# Sheet2.net
KiCad netlist of a schematic drawn in Altium Designer
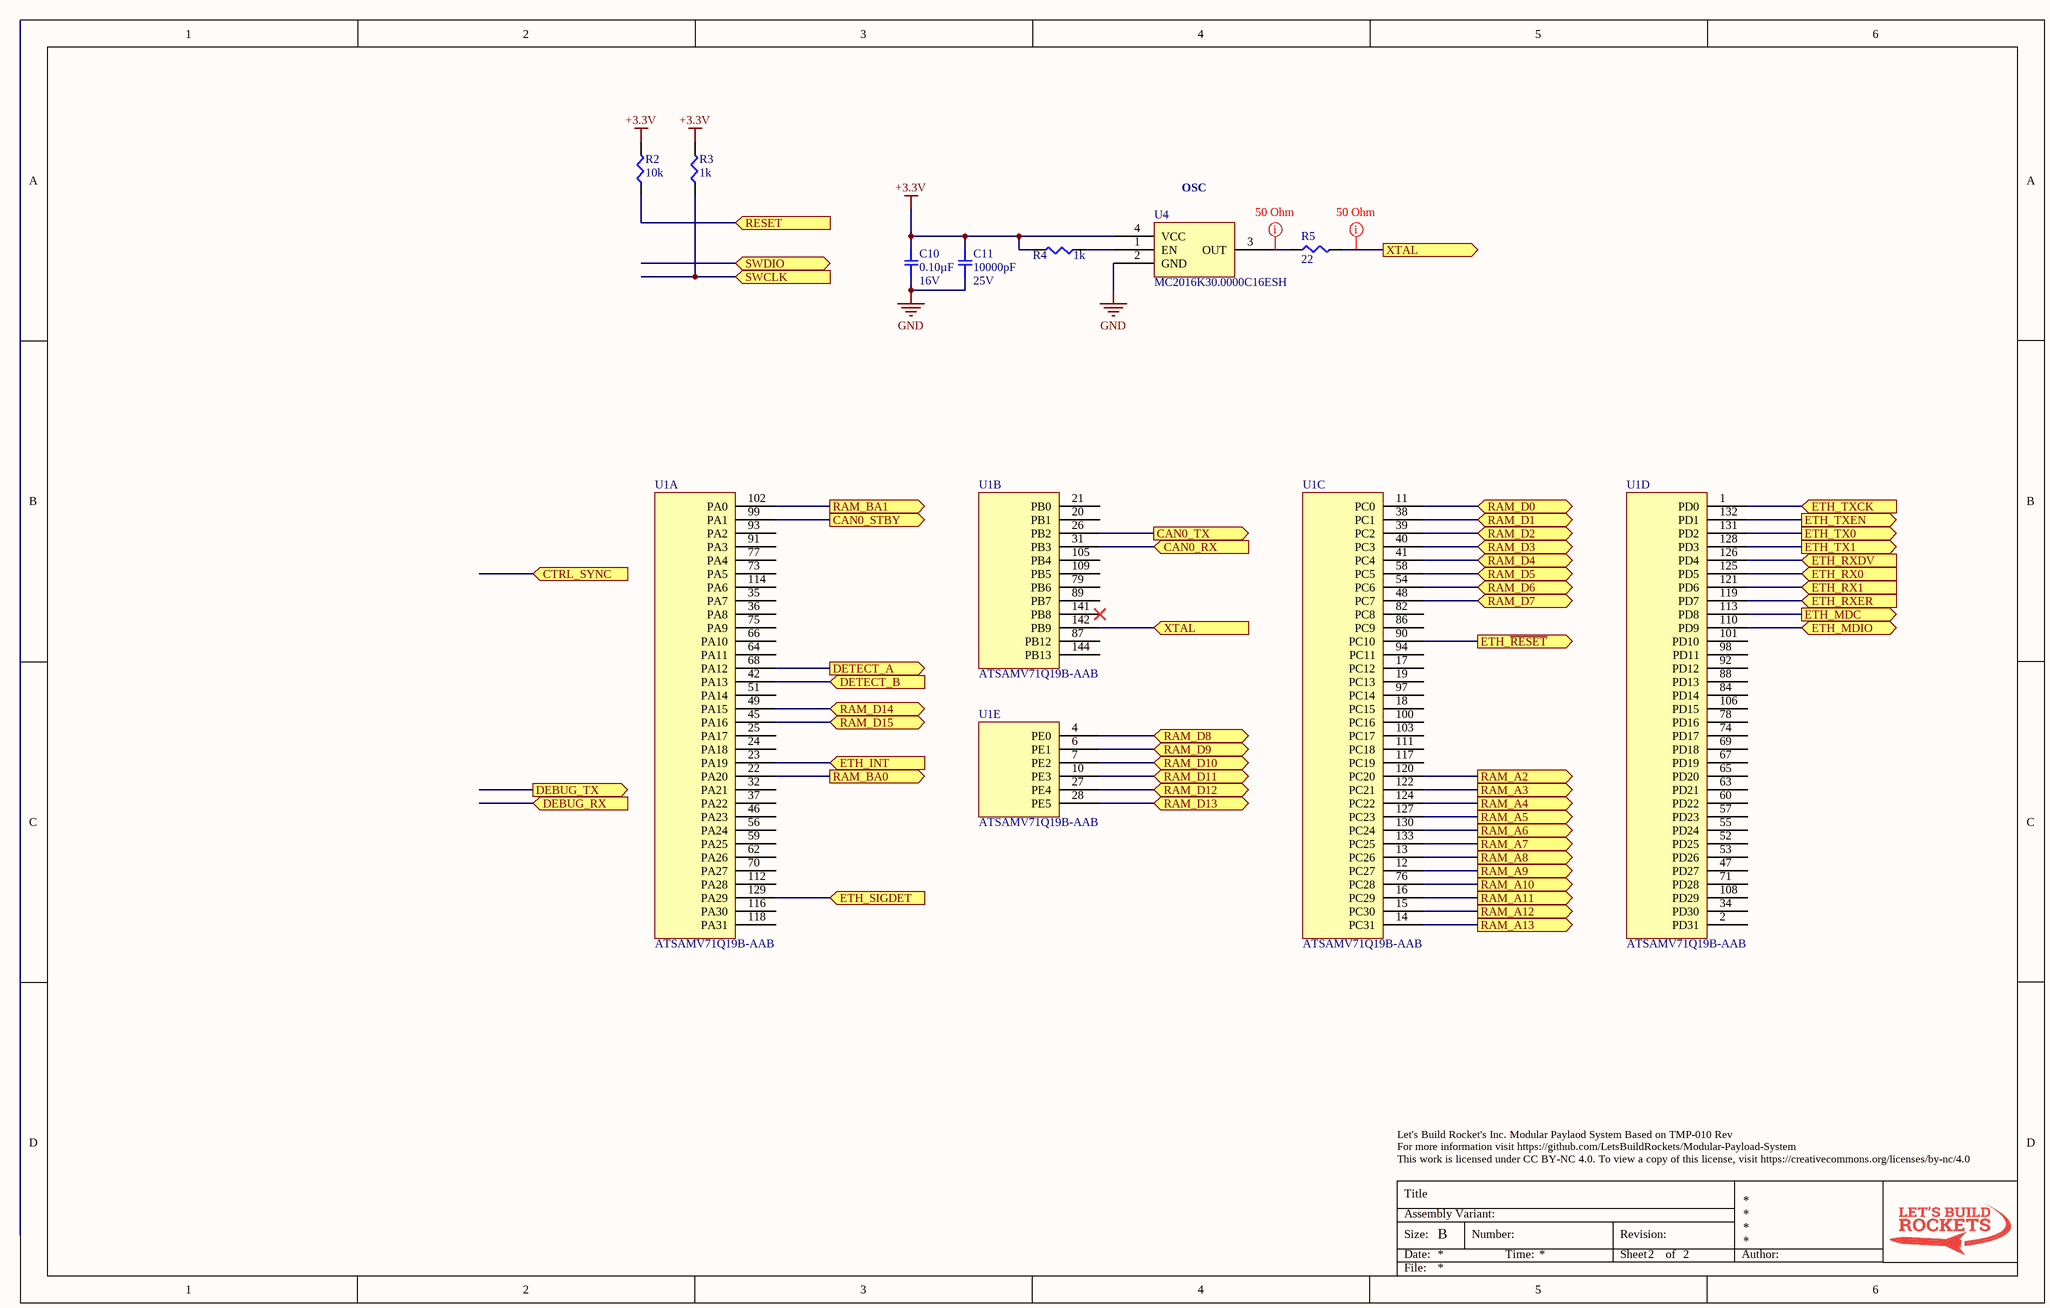
[diagram p0: Sheet2.SchDoc]

(export (version "E")
  (design (tool "Eeschema 10.0.6"))
  (components
    (comp (ref "C10")
      (value "0.10µF")
      (footprint "SMD-0402C")
      (description "CAP CER 0.1UF 16V X7R 0402")
      (fields
        (field (name "DIGI-KEY PART NUMBER") "490-4759-1-ND")
        (field (name "PART NUMBER") "GCM155R71C104KA55D")
        (field (name "VOLTAGE") "16V")
      )
      (libsource (lib "capacitor_murata_0402") (part "GCM155R71C104KA55D"))
    )
    (comp (ref "C11")
      (value "10000pF")
      (footprint "SMD-0402C")
      (description "CAP CER 10000PF 25V X7R 0402")
      (fields
        (field (name "DIGI-KEY PART NUMBER") "490-6043-1-ND")
        (field (name "PART NUMBER") "GCM155R71E103KA37D")
        (field (name "VOLTAGE") "25V")
      )
      (libsource (lib "capacitor_murata_0402") (part "GCM155R71E103KA37D"))
    )
    (comp (ref "R2")
      (value "10k")
      (footprint "SMD-0402-RES")
      (description "RES SMD 10K OHM 5% 1/10W 0402")
      (fields (field (name "PART NUMBER") "ERJ-2GEJ103X") (field (name "DIGI-KEY PART NUMBER") "P10KJCT-ND"))
      (libsource (lib "Panasonic_ERJ_0402") (part "ERJ-2GEJ103X"))
    )
    (comp (ref "R3")
      (value "1k")
      (footprint "SMD-0402-RES")
      (description "RES SMD 1K OHM 5% 1/10W 0402")
      (fields (field (name "PART NUMBER") "ERJ-2GEJ102X") (field (name "DIGI-KEY PART NUMBER") "P1.0KJCT-ND"))
      (libsource (lib "Panasonic_ERJ_0402") (part "ERJ-2GEJ102X"))
    )
    (comp (ref "R4")
      (value "1k")
      (footprint "SMD-0402-RES")
      (description "RES SMD 1K OHM 5% 1/10W 0402")
      (fields (field (name "PART NUMBER") "ERJ-2GEJ102X") (field (name "DIGI-KEY PART NUMBER") "P1.0KJCT-ND"))
      (libsource (lib "Panasonic_ERJ_0402") (part "ERJ-2GEJ102X"))
    )
    (comp (ref "R5")
      (value "22")
      (footprint "SMD-0402-RES")
      (description "RES SMD 22 OHM 1% 1/10W 0402")
      (fields
        (field (name "PART NUMBER") "ERJ-2RKF22R0X")
        (field (name "DIGI-KEY PART NUMBER") "P22.0LCT-ND")
      )
      (libsource (lib "Panasonic_ERJ_0402") (part "ERJ-2RKF22R0X"))
    )
    (comp (ref "U1")
      (value "ATSAMV71Q19B-AAB")
      (footprint "TSQFP50P2200X2200X160-144N")
      (libsource (lib "ModularPayload") (part "ATSAMV71Q19B-AAB"))
    )
    (comp (ref "U4")
      (value "MC2016K30.0000C16ESH")
      (footprint "MC2016")
      (libsource (lib "ModularPayload") (part "MC2016K30.0000C16ESH"))
    )
  )
  (nets
    (net (code "1") (name "+3.3V") (class "Default")
      (node (ref "C10") (pin "2") (pinfunction "2_2") (pintype "passive"))
      (node (ref "C11") (pin "2") (pinfunction "2_2") (pintype "passive"))
      (node (ref "R2") (pin "2") (pinfunction "2_2") (pintype "passive"))
      (node (ref "R3") (pin "2") (pinfunction "2_2") (pintype "passive"))
      (node (ref "R4") (pin "2") (pinfunction "2_2") (pintype "passive"))
      (node (ref "U4") (pin "4") (pinfunction "VCC_4") (pintype "passive"))
    )
    (net (code "2") (name "/CAN0_RX") (class "Default")
      (node (ref "U1") (pin "31") (pinfunction "PB3_31") (pintype "passive"))
    )
    (net (code "3") (name "/CAN0_STBY") (class "Default")
      (node (ref "U1") (pin "99") (pinfunction "PA1_99") (pintype "passive"))
    )
    (net (code "4") (name "/CAN0_TX") (class "Default")
      (node (ref "U1") (pin "26") (pinfunction "PB2_26") (pintype "passive"))
    )
    (net (code "8") (name "/DETECT_A") (class "Default")
      (node (ref "U1") (pin "68") (pinfunction "PA12_68") (pintype "passive"))
    )
    (net (code "9") (name "/DETECT_B") (class "Default")
      (node (ref "U1") (pin "42") (pinfunction "PA13_42") (pintype "passive"))
    )
    (net (code "10") (name "/ETH_INT") (class "Default")
      (node (ref "U1") (pin "23") (pinfunction "PA19_23") (pintype "passive"))
    )
    (net (code "11") (name "/ETH_MDC") (class "Default")
      (node (ref "U1") (pin "113") (pinfunction "PD8_113") (pintype "passive"))
    )
    (net (code "12") (name "/ETH_MDIO") (class "Default")
      (node (ref "U1") (pin "110") (pinfunction "PD9_110") (pintype "passive"))
    )
    (net (code "13") (name "/ETH_RX0") (class "Default")
      (node (ref "U1") (pin "125") (pinfunction "PD5_125") (pintype "passive"))
    )
    (net (code "14") (name "/ETH_RX1") (class "Default")
      (node (ref "U1") (pin "121") (pinfunction "PD6_121") (pintype "passive"))
    )
    (net (code "15") (name "/ETH_RXDV") (class "Default")
      (node (ref "U1") (pin "126") (pinfunction "PD4_126") (pintype "passive"))
    )
    (net (code "16") (name "/ETH_RXER") (class "Default")
      (node (ref "U1") (pin "119") (pinfunction "PD7_119") (pintype "passive"))
    )
    (net (code "17") (name "/ETH_SIGDET") (class "Default")
      (node (ref "U1") (pin "129") (pinfunction "PA29_129") (pintype "passive"))
    )
    (net (code "18") (name "/ETH_TX0") (class "Default")
      (node (ref "U1") (pin "131") (pinfunction "PD2_131") (pintype "passive"))
    )
    (net (code "19") (name "/ETH_TX1") (class "Default")
      (node (ref "U1") (pin "128") (pinfunction "PD3_128") (pintype "passive"))
    )
    (net (code "20") (name "/ETH_TXCK") (class "Default")
      (node (ref "U1") (pin "1") (pinfunction "PD0_1") (pintype "passive"))
    )
    (net (code "21") (name "/ETH_TXEN") (class "Default")
      (node (ref "U1") (pin "132") (pinfunction "PD1_132") (pintype "passive"))
    )
    (net (code "22") (name "/ETH_~{RESET}") (class "Default")
      (node (ref "U1") (pin "90") (pinfunction "PC10_90") (pintype "passive"))
    )
    (net (code "23") (name "/RAM_A2") (class "Default")
      (node (ref "U1") (pin "120") (pinfunction "PC20_120") (pintype "passive"))
    )
    (net (code "24") (name "/RAM_A3") (class "Default")
      (node (ref "U1") (pin "122") (pinfunction "PC21_122") (pintype "passive"))
    )
    (net (code "25") (name "/RAM_A4") (class "Default")
      (node (ref "U1") (pin "124") (pinfunction "PC22_124") (pintype "passive"))
    )
    (net (code "26") (name "/RAM_A5") (class "Default")
      (node (ref "U1") (pin "127") (pinfunction "PC23_127") (pintype "passive"))
    )
    (net (code "27") (name "/RAM_A6") (class "Default")
      (node (ref "U1") (pin "130") (pinfunction "PC24_130") (pintype "passive"))
    )
    (net (code "28") (name "/RAM_A7") (class "Default")
      (node (ref "U1") (pin "133") (pinfunction "PC25_133") (pintype "passive"))
    )
    (net (code "29") (name "/RAM_A8") (class "Default")
      (node (ref "U1") (pin "13") (pinfunction "PC26_13") (pintype "passive"))
    )
    (net (code "30") (name "/RAM_A9") (class "Default")
      (node (ref "U1") (pin "12") (pinfunction "PC27_12") (pintype "passive"))
    )
    (net (code "31") (name "/RAM_A10") (class "Default")
      (node (ref "U1") (pin "76") (pinfunction "PC28_76") (pintype "passive"))
    )
    (net (code "32") (name "/RAM_A11") (class "Default")
      (node (ref "U1") (pin "16") (pinfunction "PC29_16") (pintype "passive"))
    )
    (net (code "33") (name "/RAM_A12") (class "Default")
      (node (ref "U1") (pin "15") (pinfunction "PC30_15") (pintype "passive"))
    )
    (net (code "34") (name "/RAM_A13") (class "Default")
      (node (ref "U1") (pin "14") (pinfunction "PC31_14") (pintype "passive"))
    )
    (net (code "35") (name "/RAM_BA0") (class "Default")
      (node (ref "U1") (pin "22") (pinfunction "PA20_22") (pintype "passive"))
    )
    (net (code "36") (name "/RAM_BA1") (class "Default")
      (node (ref "U1") (pin "102") (pinfunction "PA0_102") (pintype "passive"))
    )
    (net (code "37") (name "/RAM_D0") (class "Default")
      (node (ref "U1") (pin "11") (pinfunction "PC0_11") (pintype "passive"))
    )
    (net (code "38") (name "/RAM_D1") (class "Default")
      (node (ref "U1") (pin "38") (pinfunction "PC1_38") (pintype "passive"))
    )
    (net (code "39") (name "/RAM_D2") (class "Default")
      (node (ref "U1") (pin "39") (pinfunction "PC2_39") (pintype "passive"))
    )
    (net (code "40") (name "/RAM_D3") (class "Default")
      (node (ref "U1") (pin "40") (pinfunction "PC3_40") (pintype "passive"))
    )
    (net (code "41") (name "/RAM_D4") (class "Default")
      (node (ref "U1") (pin "41") (pinfunction "PC4_41") (pintype "passive"))
    )
    (net (code "42") (name "/RAM_D5") (class "Default")
      (node (ref "U1") (pin "58") (pinfunction "PC5_58") (pintype "passive"))
    )
    (net (code "43") (name "/RAM_D6") (class "Default")
      (node (ref "U1") (pin "54") (pinfunction "PC6_54") (pintype "passive"))
    )
    (net (code "44") (name "/RAM_D7") (class "Default")
      (node (ref "U1") (pin "48") (pinfunction "PC7_48") (pintype "passive"))
    )
    (net (code "45") (name "/RAM_D8") (class "Default")
      (node (ref "U1") (pin "4") (pinfunction "PE0_4") (pintype "passive"))
    )
    (net (code "46") (name "/RAM_D9") (class "Default")
      (node (ref "U1") (pin "6") (pinfunction "PE1_6") (pintype "passive"))
    )
    (net (code "47") (name "/RAM_D10") (class "Default")
      (node (ref "U1") (pin "7") (pinfunction "PE2_7") (pintype "passive"))
    )
    (net (code "48") (name "/RAM_D11") (class "Default")
      (node (ref "U1") (pin "10") (pinfunction "PE3_10") (pintype "passive"))
    )
    (net (code "49") (name "/RAM_D12") (class "Default")
      (node (ref "U1") (pin "27") (pinfunction "PE4_27") (pintype "passive"))
    )
    (net (code "50") (name "/RAM_D13") (class "Default")
      (node (ref "U1") (pin "28") (pinfunction "PE5_28") (pintype "passive"))
    )
    (net (code "51") (name "/RAM_D14") (class "Default")
      (node (ref "U1") (pin "49") (pinfunction "PA15_49") (pintype "passive"))
    )
    (net (code "52") (name "/RAM_D15") (class "Default")
      (node (ref "U1") (pin "45") (pinfunction "PA16_45") (pintype "passive"))
    )
    (net (code "53") (name "/RESET") (class "Default")
      (node (ref "R2") (pin "1") (pinfunction "1_1") (pintype "passive"))
    )
    (net (code "54") (name "/SWCLK") (class "Default")
      (node (ref "R3") (pin "1") (pinfunction "1_1") (pintype "passive"))
    )
    (net (code "56") (name "/XTAL") (class "Default")
      (node (ref "R5") (pin "2") (pinfunction "2_2") (pintype "passive"))
      (node (ref "U1") (pin "142") (pinfunction "PB9_142") (pintype "passive"))
    )
    (net (code "57") (name "GND") (class "Default")
      (node (ref "C10") (pin "1") (pinfunction "1_1") (pintype "passive"))
      (node (ref "C11") (pin "1") (pinfunction "1_1") (pintype "passive"))
      (node (ref "U4") (pin "2") (pinfunction "GND_2") (pintype "passive"))
    )
    (net (code "58") (name "Net-(U4-EN)") (class "Default")
      (node (ref "R4") (pin "1") (pinfunction "1_1") (pintype "passive"))
      (node (ref "U4") (pin "1") (pinfunction "EN_1") (pintype "passive"))
    )
    (net (code "59") (name "Net-(U4-OUT)") (class "Default")
      (node (ref "R5") (pin "1") (pinfunction "1_1") (pintype "passive"))
      (node (ref "U4") (pin "3") (pinfunction "OUT_3") (pintype "passive"))
    )
    (net (code "60") (name "unconnected-(U1A-PA2-Pad93)") (class "Default")
      (node (ref "U1") (pin "93") (pinfunction "PA2_93") (pintype "passive"))
    )
    (net (code "61") (name "unconnected-(U1A-PA3-Pad91)") (class "Default")
      (node (ref "U1") (pin "91") (pinfunction "PA3_91") (pintype "passive"))
    )
    (net (code "62") (name "unconnected-(U1A-PA4-Pad77)") (class "Default")
      (node (ref "U1") (pin "77") (pinfunction "PA4_77") (pintype "passive"))
    )
    (net (code "63") (name "unconnected-(U1A-PA5-Pad73)") (class "Default")
      (node (ref "U1") (pin "73") (pinfunction "PA5_73") (pintype "passive"))
    )
    (net (code "64") (name "unconnected-(U1A-PA6-Pad114)") (class "Default")
      (node (ref "U1") (pin "114") (pinfunction "PA6_114") (pintype "passive"))
    )
    (net (code "65") (name "unconnected-(U1A-PA7-Pad35)") (class "Default")
      (node (ref "U1") (pin "35") (pinfunction "PA7_35") (pintype "passive"))
    )
    (net (code "66") (name "unconnected-(U1A-PA8-Pad36)") (class "Default")
      (node (ref "U1") (pin "36") (pinfunction "PA8_36") (pintype "passive"))
    )
    (net (code "67") (name "unconnected-(U1A-PA9-Pad75)") (class "Default")
      (node (ref "U1") (pin "75") (pinfunction "PA9_75") (pintype "passive"))
    )
    (net (code "68") (name "unconnected-(U1A-PA10-Pad66)") (class "Default")
      (node (ref "U1") (pin "66") (pinfunction "PA10_66") (pintype "passive"))
    )
    (net (code "69") (name "unconnected-(U1A-PA11-Pad64)") (class "Default")
      (node (ref "U1") (pin "64") (pinfunction "PA11_64") (pintype "passive"))
    )
    (net (code "70") (name "unconnected-(U1A-PA14-Pad51)") (class "Default")
      (node (ref "U1") (pin "51") (pinfunction "PA14_51") (pintype "passive"))
    )
    (net (code "71") (name "unconnected-(U1A-PA17-Pad25)") (class "Default")
      (node (ref "U1") (pin "25") (pinfunction "PA17_25") (pintype "passive"))
    )
    (net (code "72") (name "unconnected-(U1A-PA18-Pad24)") (class "Default")
      (node (ref "U1") (pin "24") (pinfunction "PA18_24") (pintype "passive"))
    )
    (net (code "73") (name "unconnected-(U1A-PA21-Pad32)") (class "Default")
      (node (ref "U1") (pin "32") (pinfunction "PA21_32") (pintype "passive"))
    )
    (net (code "74") (name "unconnected-(U1A-PA22-Pad37)") (class "Default")
      (node (ref "U1") (pin "37") (pinfunction "PA22_37") (pintype "passive"))
    )
    (net (code "75") (name "unconnected-(U1A-PA23-Pad46)") (class "Default")
      (node (ref "U1") (pin "46") (pinfunction "PA23_46") (pintype "passive"))
    )
    (net (code "76") (name "unconnected-(U1A-PA24-Pad56)") (class "Default")
      (node (ref "U1") (pin "56") (pinfunction "PA24_56") (pintype "passive"))
    )
    (net (code "77") (name "unconnected-(U1A-PA25-Pad59)") (class "Default")
      (node (ref "U1") (pin "59") (pinfunction "PA25_59") (pintype "passive"))
    )
    (net (code "78") (name "unconnected-(U1A-PA26-Pad62)") (class "Default")
      (node (ref "U1") (pin "62") (pinfunction "PA26_62") (pintype "passive"))
    )
    (net (code "79") (name "unconnected-(U1A-PA27-Pad70)") (class "Default")
      (node (ref "U1") (pin "70") (pinfunction "PA27_70") (pintype "passive"))
    )
    (net (code "80") (name "unconnected-(U1A-PA28-Pad112)") (class "Default")
      (node (ref "U1") (pin "112") (pinfunction "PA28_112") (pintype "passive"))
    )
    (net (code "81") (name "unconnected-(U1A-PA30-Pad116)") (class "Default")
      (node (ref "U1") (pin "116") (pinfunction "PA30_116") (pintype "passive"))
    )
    (net (code "82") (name "unconnected-(U1A-PA31-Pad118)") (class "Default")
      (node (ref "U1") (pin "118") (pinfunction "PA31_118") (pintype "passive"))
    )
    (net (code "83") (name "unconnected-(U1B-PB0-Pad21)") (class "Default")
      (node (ref "U1") (pin "21") (pinfunction "PB0_21") (pintype "passive"))
    )
    (net (code "84") (name "unconnected-(U1B-PB1-Pad20)") (class "Default")
      (node (ref "U1") (pin "20") (pinfunction "PB1_20") (pintype "passive"))
    )
    (net (code "85") (name "unconnected-(U1B-PB4-Pad105)") (class "Default")
      (node (ref "U1") (pin "105") (pinfunction "PB4_105") (pintype "passive"))
    )
    (net (code "86") (name "unconnected-(U1B-PB5-Pad109)") (class "Default")
      (node (ref "U1") (pin "109") (pinfunction "PB5_109") (pintype "passive"))
    )
    (net (code "87") (name "unconnected-(U1B-PB6-Pad79)") (class "Default")
      (node (ref "U1") (pin "79") (pinfunction "PB6_79") (pintype "passive"))
    )
    (net (code "88") (name "unconnected-(U1B-PB7-Pad89)") (class "Default")
      (node (ref "U1") (pin "89") (pinfunction "PB7_89") (pintype "passive"))
    )
    (net (code "89") (name "unconnected-(U1B-PB8-Pad141)") (class "Default")
      (node (ref "U1") (pin "141") (pinfunction "PB8_141") (pintype "passive+no_connect"))
    )
    (net (code "90") (name "unconnected-(U1B-PB12-Pad87)") (class "Default")
      (node (ref "U1") (pin "87") (pinfunction "PB12_87") (pintype "passive"))
    )
    (net (code "91") (name "unconnected-(U1B-PB13-Pad144)") (class "Default")
      (node (ref "U1") (pin "144") (pinfunction "PB13_144") (pintype "passive"))
    )
    (net (code "92") (name "unconnected-(U1C-PC8-Pad82)") (class "Default")
      (node (ref "U1") (pin "82") (pinfunction "PC8_82") (pintype "passive"))
    )
    (net (code "93") (name "unconnected-(U1C-PC9-Pad86)") (class "Default")
      (node (ref "U1") (pin "86") (pinfunction "PC9_86") (pintype "passive"))
    )
    (net (code "94") (name "unconnected-(U1C-PC11-Pad94)") (class "Default")
      (node (ref "U1") (pin "94") (pinfunction "PC11_94") (pintype "passive"))
    )
    (net (code "95") (name "unconnected-(U1C-PC12-Pad17)") (class "Default")
      (node (ref "U1") (pin "17") (pinfunction "PC12_17") (pintype "passive"))
    )
    (net (code "96") (name "unconnected-(U1C-PC13-Pad19)") (class "Default")
      (node (ref "U1") (pin "19") (pinfunction "PC13_19") (pintype "passive"))
    )
    (net (code "97") (name "unconnected-(U1C-PC14-Pad97)") (class "Default")
      (node (ref "U1") (pin "97") (pinfunction "PC14_97") (pintype "passive"))
    )
    (net (code "98") (name "unconnected-(U1C-PC15-Pad18)") (class "Default")
      (node (ref "U1") (pin "18") (pinfunction "PC15_18") (pintype "passive"))
    )
    (net (code "99") (name "unconnected-(U1C-PC16-Pad100)") (class "Default")
      (node (ref "U1") (pin "100") (pinfunction "PC16_100") (pintype "passive"))
    )
    (net (code "100") (name "unconnected-(U1C-PC17-Pad103)") (class "Default")
      (node (ref "U1") (pin "103") (pinfunction "PC17_103") (pintype "passive"))
    )
    (net (code "101") (name "unconnected-(U1C-PC18-Pad111)") (class "Default")
      (node (ref "U1") (pin "111") (pinfunction "PC18_111") (pintype "passive"))
    )
    (net (code "102") (name "unconnected-(U1C-PC19-Pad117)") (class "Default")
      (node (ref "U1") (pin "117") (pinfunction "PC19_117") (pintype "passive"))
    )
    (net (code "103") (name "unconnected-(U1D-PD10-Pad101)") (class "Default")
      (node (ref "U1") (pin "101") (pinfunction "PD10_101") (pintype "passive"))
    )
    (net (code "104") (name "unconnected-(U1D-PD11-Pad98)") (class "Default")
      (node (ref "U1") (pin "98") (pinfunction "PD11_98") (pintype "passive"))
    )
    (net (code "105") (name "unconnected-(U1D-PD12-Pad92)") (class "Default")
      (node (ref "U1") (pin "92") (pinfunction "PD12_92") (pintype "passive"))
    )
    (net (code "106") (name "unconnected-(U1D-PD13-Pad88)") (class "Default")
      (node (ref "U1") (pin "88") (pinfunction "PD13_88") (pintype "passive"))
    )
    (net (code "107") (name "unconnected-(U1D-PD14-Pad84)") (class "Default")
      (node (ref "U1") (pin "84") (pinfunction "PD14_84") (pintype "passive"))
    )
    (net (code "108") (name "unconnected-(U1D-PD15-Pad106)") (class "Default")
      (node (ref "U1") (pin "106") (pinfunction "PD15_106") (pintype "passive"))
    )
    (net (code "109") (name "unconnected-(U1D-PD16-Pad78)") (class "Default")
      (node (ref "U1") (pin "78") (pinfunction "PD16_78") (pintype "passive"))
    )
    (net (code "110") (name "unconnected-(U1D-PD17-Pad74)") (class "Default")
      (node (ref "U1") (pin "74") (pinfunction "PD17_74") (pintype "passive"))
    )
    (net (code "111") (name "unconnected-(U1D-PD18-Pad69)") (class "Default")
      (node (ref "U1") (pin "69") (pinfunction "PD18_69") (pintype "passive"))
    )
    (net (code "112") (name "unconnected-(U1D-PD19-Pad67)") (class "Default")
      (node (ref "U1") (pin "67") (pinfunction "PD19_67") (pintype "passive"))
    )
    (net (code "113") (name "unconnected-(U1D-PD20-Pad65)") (class "Default")
      (node (ref "U1") (pin "65") (pinfunction "PD20_65") (pintype "passive"))
    )
    (net (code "114") (name "unconnected-(U1D-PD21-Pad63)") (class "Default")
      (node (ref "U1") (pin "63") (pinfunction "PD21_63") (pintype "passive"))
    )
    (net (code "115") (name "unconnected-(U1D-PD22-Pad60)") (class "Default")
      (node (ref "U1") (pin "60") (pinfunction "PD22_60") (pintype "passive"))
    )
    (net (code "116") (name "unconnected-(U1D-PD23-Pad57)") (class "Default")
      (node (ref "U1") (pin "57") (pinfunction "PD23_57") (pintype "passive"))
    )
    (net (code "117") (name "unconnected-(U1D-PD24-Pad55)") (class "Default")
      (node (ref "U1") (pin "55") (pinfunction "PD24_55") (pintype "passive"))
    )
    (net (code "118") (name "unconnected-(U1D-PD25-Pad52)") (class "Default")
      (node (ref "U1") (pin "52") (pinfunction "PD25_52") (pintype "passive"))
    )
    (net (code "119") (name "unconnected-(U1D-PD26-Pad53)") (class "Default")
      (node (ref "U1") (pin "53") (pinfunction "PD26_53") (pintype "passive"))
    )
    (net (code "120") (name "unconnected-(U1D-PD27-Pad47)") (class "Default")
      (node (ref "U1") (pin "47") (pinfunction "PD27_47") (pintype "passive"))
    )
    (net (code "121") (name "unconnected-(U1D-PD28-Pad71)") (class "Default")
      (node (ref "U1") (pin "71") (pinfunction "PD28_71") (pintype "passive"))
    )
    (net (code "122") (name "unconnected-(U1D-PD29-Pad108)") (class "Default")
      (node (ref "U1") (pin "108") (pinfunction "PD29_108") (pintype "passive"))
    )
    (net (code "123") (name "unconnected-(U1D-PD30-Pad34)") (class "Default")
      (node (ref "U1") (pin "34") (pinfunction "PD30_34") (pintype "passive"))
    )
    (net (code "124") (name "unconnected-(U1D-PD31-Pad2)") (class "Default")
      (node (ref "U1") (pin "2") (pinfunction "PD31_2") (pintype "passive"))
    )
  )
)
